# IEEEcounter.net
KiCad netlist of a schematic drawn in EAGLE
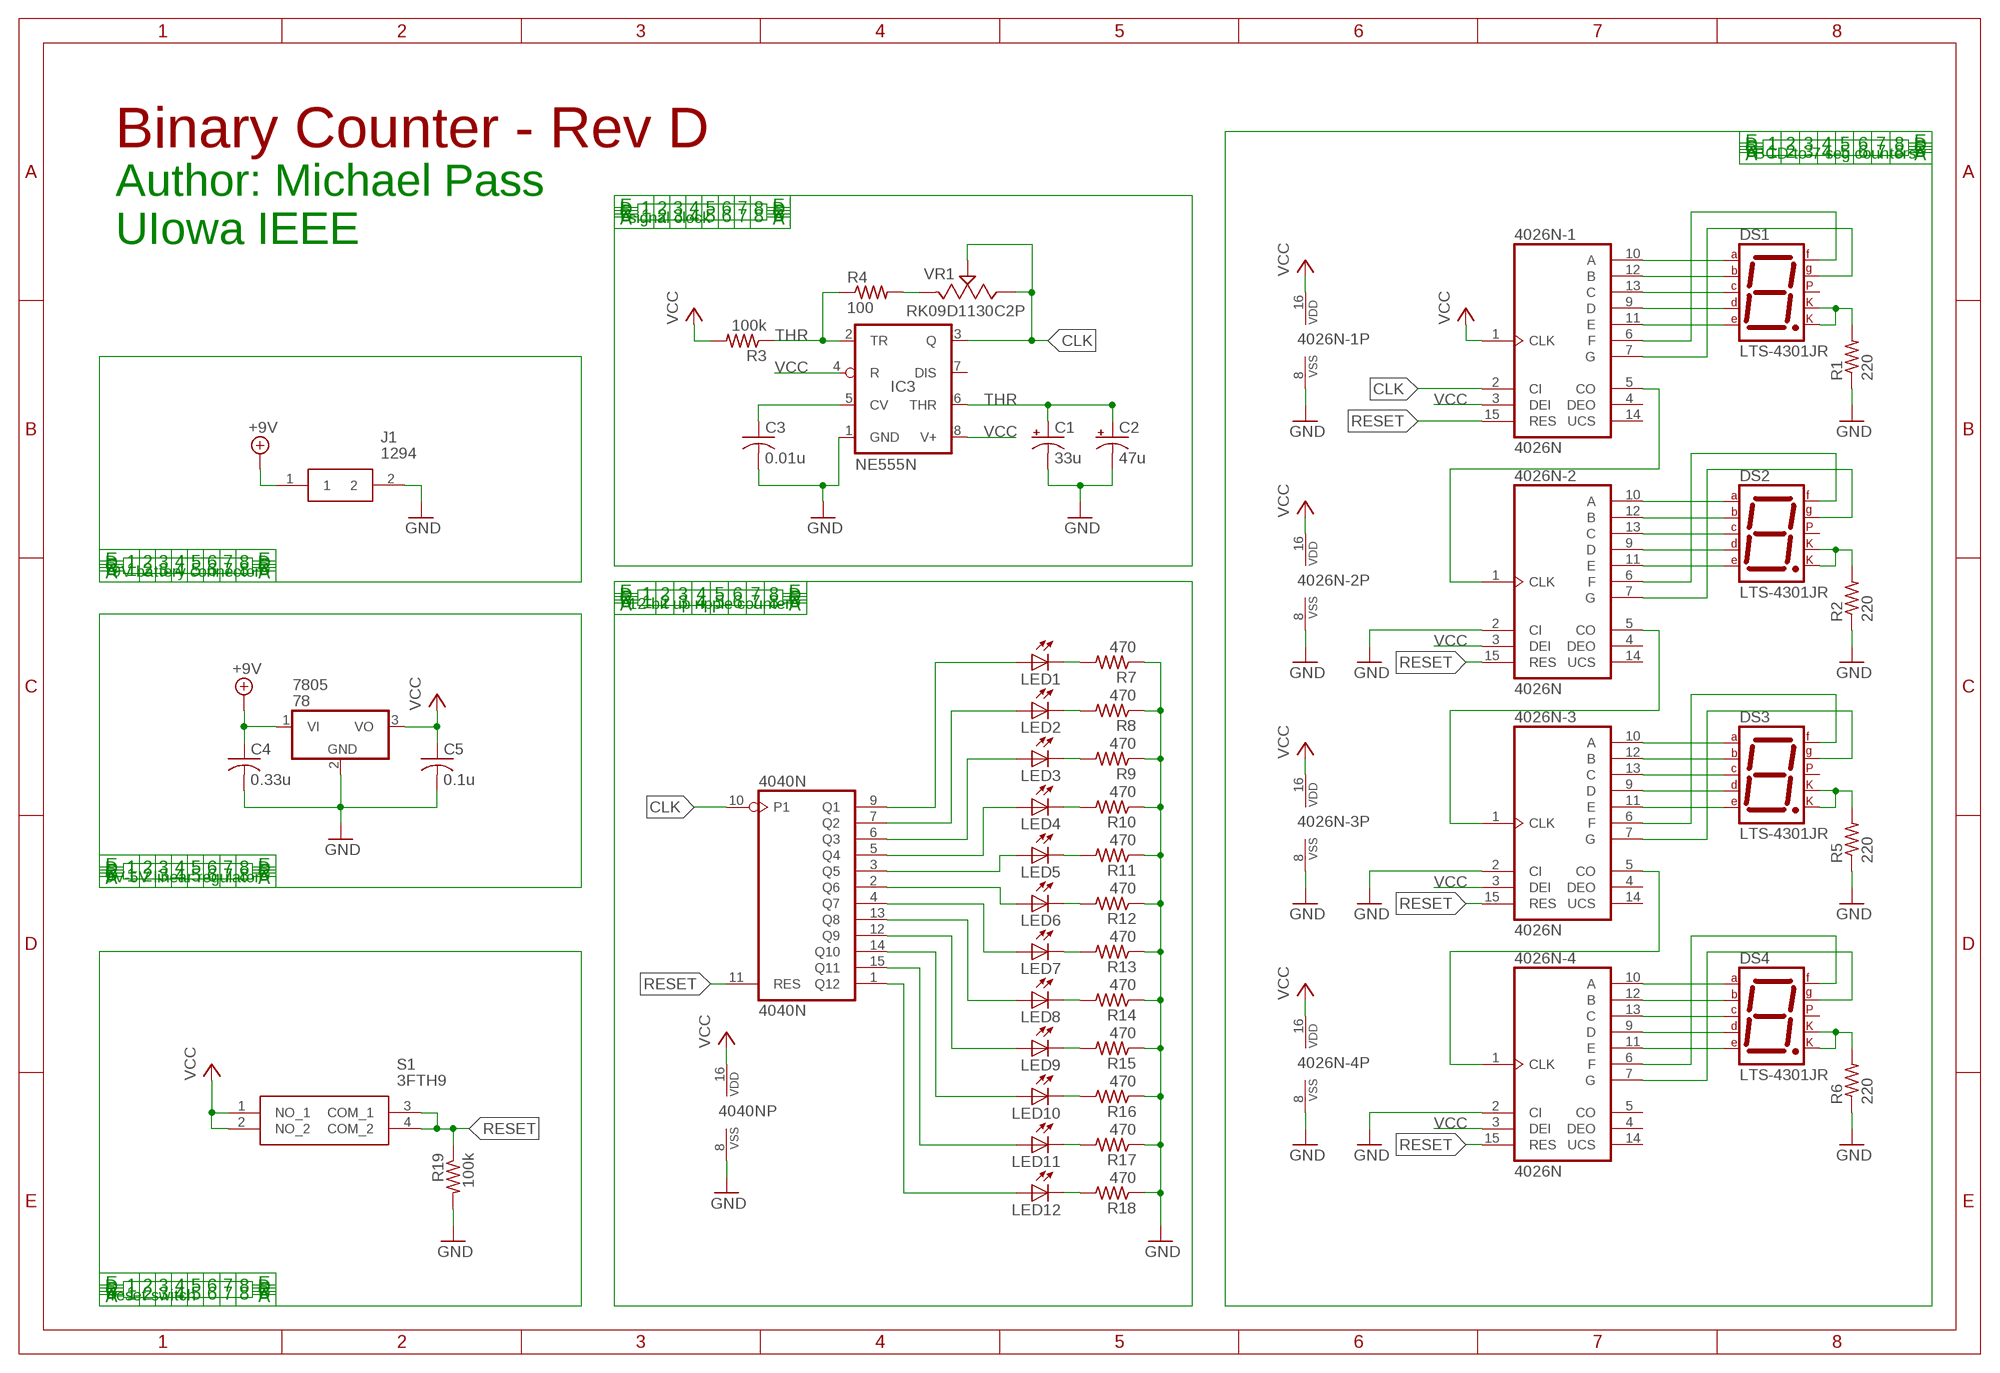
[diagram p0: schematic, sheet 1]

(export (version "E")
  (design (tool "Eeschema 10.0.6"))
  (components
    (comp (ref "4026N-1")
      (value "4026N")
      (footprint "eagle-import:DIL16")
      (libsource (lib "eagle-import") (part "4026N"))
    )
    (comp (ref "4026N-2")
      (value "4026N")
      (footprint "eagle-import:DIL16")
      (libsource (lib "eagle-import") (part "4026N"))
    )
    (comp (ref "4026N-3")
      (value "4026N")
      (footprint "eagle-import:DIL16")
      (libsource (lib "eagle-import") (part "4026N"))
    )
    (comp (ref "4026N-4")
      (value "4026N")
      (footprint "eagle-import:DIL16")
      (libsource (lib "eagle-import") (part "4026N"))
    )
    (comp (ref "4040N")
      (value "4040N")
      (footprint "eagle-import:DIL16")
      (libsource (lib "eagle-import") (part "4040N"))
    )
    (comp (ref "7805")
      (value "78")
      (footprint "eagle-import:TO220H")
      (libsource (lib "eagle-import") (part "78"))
    )
    (comp (ref "C1")
      (value "33u")
      (footprint "eagle-import:E2,5-6")
      (libsource (lib "eagle-import") (part "CPOL-USE2.5-6"))
    )
    (comp (ref "C2")
      (value "47u")
      (footprint "eagle-import:E2,5-6")
      (libsource (lib "eagle-import") (part "CPOL-USE2.5-6"))
    )
    (comp (ref "C3")
      (value "0.01u")
      (footprint "eagle-import:C050-025X075")
      (libsource (lib "eagle-import") (part "C-US050-025X075"))
    )
    (comp (ref "C4")
      (value "0.33u")
      (footprint "eagle-import:C1210")
      (libsource (lib "eagle-import") (part "C-USC1210"))
    )
    (comp (ref "C5")
      (value "0.1u")
      (footprint "eagle-import:C1210")
      (libsource (lib "eagle-import") (part "C-USC1210"))
    )
    (comp (ref "DS1")
      (value "LTS-4301JR")
      (footprint "eagle-import:DIPS762W50P254L1290H700Q10N")
      (fields (field (name "MOUSER_PART_NUMBER") "859-LTS-4301JR"))
      (libsource (lib "eagle-import") (part "LTS-4301JR"))
    )
    (comp (ref "DS2")
      (value "LTS-4301JR")
      (footprint "eagle-import:DIPS762W50P254L1290H700Q10N")
      (fields (field (name "MOUSER_PART_NUMBER") "859-LTS-4301JR"))
      (libsource (lib "eagle-import") (part "LTS-4301JR"))
    )
    (comp (ref "DS3")
      (value "LTS-4301JR")
      (footprint "eagle-import:DIPS762W50P254L1290H700Q10N")
      (fields (field (name "MOUSER_PART_NUMBER") "859-LTS-4301JR"))
      (libsource (lib "eagle-import") (part "LTS-4301JR"))
    )
    (comp (ref "DS4")
      (value "LTS-4301JR")
      (footprint "eagle-import:DIPS762W50P254L1290H700Q10N")
      (fields (field (name "MOUSER_PART_NUMBER") "859-LTS-4301JR"))
      (libsource (lib "eagle-import") (part "LTS-4301JR"))
    )
    (comp (ref "IC3")
      (value "NE555N")
      (footprint "eagle-import:DIL08")
      (libsource (lib "eagle-import") (part "555NNE"))
    )
    (comp (ref "J1")
      (value "1294")
      (footprint "eagle-import:1294")
      (fields (field (name "MOUSER_PART_NUMBER") "534-1294") (field (name "RS_PART_NUMBER") "1725845"))
      (libsource (lib "eagle-import") (part "1294"))
    )
    (comp (ref "LED1")
      (value "LED5MM")
      (footprint "eagle-import:LED5MM")
      (libsource (lib "eagle-import") (part "LED5MM"))
    )
    (comp (ref "LED2")
      (value "LED5MM")
      (footprint "eagle-import:LED5MM")
      (libsource (lib "eagle-import") (part "LED5MM"))
    )
    (comp (ref "LED3")
      (value "LED5MM")
      (footprint "eagle-import:LED5MM")
      (libsource (lib "eagle-import") (part "LED5MM"))
    )
    (comp (ref "LED4")
      (value "LED5MM")
      (footprint "eagle-import:LED5MM")
      (libsource (lib "eagle-import") (part "LED5MM"))
    )
    (comp (ref "LED5")
      (value "LED5MM")
      (footprint "eagle-import:LED5MM")
      (libsource (lib "eagle-import") (part "LED5MM"))
    )
    (comp (ref "LED6")
      (value "LED5MM")
      (footprint "eagle-import:LED5MM")
      (libsource (lib "eagle-import") (part "LED5MM"))
    )
    (comp (ref "LED7")
      (value "LED5MM")
      (footprint "eagle-import:LED5MM")
      (libsource (lib "eagle-import") (part "LED5MM"))
    )
    (comp (ref "LED8")
      (value "LED5MM")
      (footprint "eagle-import:LED5MM")
      (libsource (lib "eagle-import") (part "LED5MM"))
    )
    (comp (ref "LED9")
      (value "LED5MM")
      (footprint "eagle-import:LED5MM")
      (libsource (lib "eagle-import") (part "LED5MM"))
    )
    (comp (ref "LED10")
      (value "LED5MM")
      (footprint "eagle-import:LED5MM")
      (libsource (lib "eagle-import") (part "LED5MM"))
    )
    (comp (ref "LED11")
      (value "LED5MM")
      (footprint "eagle-import:LED5MM")
      (libsource (lib "eagle-import") (part "LED5MM"))
    )
    (comp (ref "LED12")
      (value "LED5MM")
      (footprint "eagle-import:LED5MM")
      (libsource (lib "eagle-import") (part "LED5MM"))
    )
    (comp (ref "R1")
      (value "220")
      (footprint "eagle-import:R1210")
      (libsource (lib "eagle-import") (part "R-US_R1210"))
    )
    (comp (ref "R2")
      (value "220")
      (footprint "eagle-import:R1210")
      (libsource (lib "eagle-import") (part "R-US_R1210"))
    )
    (comp (ref "R3")
      (value "100k")
      (footprint "eagle-import:R1210")
      (libsource (lib "eagle-import") (part "R-US_R1210"))
    )
    (comp (ref "R4")
      (value "100")
      (footprint "eagle-import:R1210")
      (libsource (lib "eagle-import") (part "R-US_R1210"))
    )
    (comp (ref "R5")
      (value "220")
      (footprint "eagle-import:R1210")
      (libsource (lib "eagle-import") (part "R-US_R1210"))
    )
    (comp (ref "R6")
      (value "220")
      (footprint "eagle-import:R1210")
      (libsource (lib "eagle-import") (part "R-US_R1210"))
    )
    (comp (ref "R7")
      (value "470")
      (footprint "eagle-import:R1210")
      (libsource (lib "eagle-import") (part "R-US_R1210"))
    )
    (comp (ref "R8")
      (value "470")
      (footprint "eagle-import:R1210")
      (libsource (lib "eagle-import") (part "R-US_R1210"))
    )
    (comp (ref "R9")
      (value "470")
      (footprint "eagle-import:R1210")
      (libsource (lib "eagle-import") (part "R-US_R1210"))
    )
    (comp (ref "R10")
      (value "470")
      (footprint "eagle-import:R1210")
      (libsource (lib "eagle-import") (part "R-US_R1210"))
    )
    (comp (ref "R11")
      (value "470")
      (footprint "eagle-import:R1210")
      (libsource (lib "eagle-import") (part "R-US_R1210"))
    )
    (comp (ref "R12")
      (value "470")
      (footprint "eagle-import:R1210")
      (libsource (lib "eagle-import") (part "R-US_R1210"))
    )
    (comp (ref "R13")
      (value "470")
      (footprint "eagle-import:R1210")
      (libsource (lib "eagle-import") (part "R-US_R1210"))
    )
    (comp (ref "R14")
      (value "470")
      (footprint "eagle-import:R1210")
      (libsource (lib "eagle-import") (part "R-US_R1210"))
    )
    (comp (ref "R15")
      (value "470")
      (footprint "eagle-import:R1210")
      (libsource (lib "eagle-import") (part "R-US_R1210"))
    )
    (comp (ref "R16")
      (value "470")
      (footprint "eagle-import:R1210")
      (libsource (lib "eagle-import") (part "R-US_R1210"))
    )
    (comp (ref "R17")
      (value "470")
      (footprint "eagle-import:R1210")
      (libsource (lib "eagle-import") (part "R-US_R1210"))
    )
    (comp (ref "R18")
      (value "470")
      (footprint "eagle-import:R1210")
      (libsource (lib "eagle-import") (part "R-US_R1210"))
    )
    (comp (ref "R19")
      (value "100k")
      (footprint "eagle-import:R1210")
      (libsource (lib "eagle-import") (part "R-US_R1210"))
    )
    (comp (ref "S1")
      (value "3FTH9")
      (footprint "eagle-import:3FTH9")
      (fields (field (name "MOUSER_PART_NUMBER") "642-3FTH9"))
      (libsource (lib "eagle-import") (part "3FTH9"))
    )
    (comp (ref "VR1")
      (value "RK09D1130C2P")
      (footprint "eagle-import:RK09D1130C3C")
      (fields
        (field (name "MOUSER_PART_NUMBER") "688-RK09D1130C2P")
        (field (name "RS_PART_NUMBER") "1726272")
      )
      (libsource (lib "eagle-import") (part "RK09D1130C2P"))
    )
  )
  (nets
    (net (code "1") (name "+9V") (class "Default")
      (node (ref "7805") (pin "1") (pinfunction "VI_1") (pintype "input"))
      (node (ref "C4") (pin "1") (pinfunction "1_1") (pintype "passive"))
      (node (ref "J1") (pin "1") (pinfunction "1_1") (pintype "bidirectional"))
    )
    (net (code "2") (name "/THR") (class "Default")
      (node (ref "C1") (pin "+") (pinfunction "+_+") (pintype "passive"))
      (node (ref "C2") (pin "+") (pinfunction "+_+") (pintype "passive"))
      (node (ref "IC3") (pin "2") (pinfunction "TR_2") (pintype "input"))
      (node (ref "IC3") (pin "6") (pinfunction "THR_6") (pintype "input"))
      (node (ref "R3") (pin "1") (pinfunction "1_1") (pintype "passive"))
      (node (ref "R4") (pin "1") (pinfunction "1_1") (pintype "passive"))
    )
    (net (code "3") (name "CLK") (class "Default")
      (node (ref "4026N-1") (pin "2") (pinfunction "CI_2") (pintype "input"))
      (node (ref "4040N") (pin "10") (pinfunction "P1_10") (pintype "input"))
      (node (ref "IC3") (pin "3") (pinfunction "Q_3") (pintype "output"))
      (node (ref "VR1") (pin "2") (pinfunction "2_2") (pintype "passive"))
      (node (ref "VR1") (pin "3") (pinfunction "3_3") (pintype "passive"))
    )
    (net (code "4") (name "GND") (class "Default")
      (node (ref "4026N-1") (pin "8") (pinfunction "VSS_8") (pintype "power_in"))
      (node (ref "4026N-2") (pin "2") (pinfunction "CI_2") (pintype "input"))
      (node (ref "4026N-2") (pin "8") (pinfunction "VSS_8") (pintype "power_in"))
      (node (ref "4026N-3") (pin "2") (pinfunction "CI_2") (pintype "input"))
      (node (ref "4026N-3") (pin "8") (pinfunction "VSS_8") (pintype "power_in"))
      (node (ref "4026N-4") (pin "2") (pinfunction "CI_2") (pintype "input"))
      (node (ref "4026N-4") (pin "8") (pinfunction "VSS_8") (pintype "power_in"))
      (node (ref "4040N") (pin "8") (pinfunction "VSS_8") (pintype "power_in"))
      (node (ref "7805") (pin "2") (pinfunction "GND_2") (pintype "passive"))
      (node (ref "C1") (pin "-") (pinfunction "-_-") (pintype "passive"))
      (node (ref "C2") (pin "-") (pinfunction "-_-") (pintype "passive"))
      (node (ref "C3") (pin "2") (pinfunction "2_2") (pintype "passive"))
      (node (ref "C4") (pin "2") (pinfunction "2_2") (pintype "passive"))
      (node (ref "C5") (pin "2") (pinfunction "2_2") (pintype "passive"))
      (node (ref "IC3") (pin "1") (pinfunction "GND_1") (pintype "power_in"))
      (node (ref "J1") (pin "2") (pinfunction "2_2") (pintype "bidirectional"))
      (node (ref "R1") (pin "1") (pinfunction "1_1") (pintype "passive"))
      (node (ref "R10") (pin "1") (pinfunction "1_1") (pintype "passive"))
      (node (ref "R11") (pin "1") (pinfunction "1_1") (pintype "passive"))
      (node (ref "R12") (pin "1") (pinfunction "1_1") (pintype "passive"))
      (node (ref "R13") (pin "1") (pinfunction "1_1") (pintype "passive"))
      (node (ref "R14") (pin "1") (pinfunction "1_1") (pintype "passive"))
      (node (ref "R15") (pin "1") (pinfunction "1_1") (pintype "passive"))
      (node (ref "R16") (pin "1") (pinfunction "1_1") (pintype "passive"))
      (node (ref "R17") (pin "1") (pinfunction "1_1") (pintype "passive"))
      (node (ref "R18") (pin "1") (pinfunction "1_1") (pintype "passive"))
      (node (ref "R19") (pin "2") (pinfunction "2_2") (pintype "passive"))
      (node (ref "R2") (pin "1") (pinfunction "1_1") (pintype "passive"))
      (node (ref "R5") (pin "1") (pinfunction "1_1") (pintype "passive"))
      (node (ref "R6") (pin "1") (pinfunction "1_1") (pintype "passive"))
      (node (ref "R7") (pin "1") (pinfunction "1_1") (pintype "passive"))
      (node (ref "R8") (pin "1") (pinfunction "1_1") (pintype "passive"))
      (node (ref "R9") (pin "1") (pinfunction "1_1") (pintype "passive"))
    )
    (net (code "5") (name "Net-(4026N-1A-A)") (class "Default")
      (node (ref "4026N-1") (pin "10") (pinfunction "A_10") (pintype "output"))
      (node (ref "DS1") (pin "10") (pinfunction "A_10") (pintype "passive"))
    )
    (net (code "6") (name "Net-(4026N-1A-B)") (class "Default")
      (node (ref "4026N-1") (pin "12") (pinfunction "B_12") (pintype "output"))
      (node (ref "DS1") (pin "9") (pinfunction "B_9") (pintype "passive"))
    )
    (net (code "7") (name "Net-(4026N-1A-C)") (class "Default")
      (node (ref "4026N-1") (pin "13") (pinfunction "C_13") (pintype "output"))
      (node (ref "DS1") (pin "7") (pinfunction "C_7") (pintype "passive"))
    )
    (net (code "8") (name "Net-(4026N-1A-CO)") (class "Default")
      (node (ref "4026N-1") (pin "5") (pinfunction "CO_5") (pintype "output"))
      (node (ref "4026N-2") (pin "1") (pinfunction "CLK_1") (pintype "input"))
    )
    (net (code "9") (name "Net-(4026N-1A-D)") (class "Default")
      (node (ref "4026N-1") (pin "9") (pinfunction "D_9") (pintype "output"))
      (node (ref "DS1") (pin "5") (pinfunction "D_5") (pintype "passive"))
    )
    (net (code "10") (name "Net-(4026N-1A-E)") (class "Default")
      (node (ref "4026N-1") (pin "11") (pinfunction "E_11") (pintype "output"))
      (node (ref "DS1") (pin "4") (pinfunction "E_4") (pintype "passive"))
    )
    (net (code "11") (name "Net-(4026N-1A-F)") (class "Default")
      (node (ref "4026N-1") (pin "6") (pinfunction "F_6") (pintype "output"))
      (node (ref "DS1") (pin "2") (pinfunction "F_2") (pintype "passive"))
    )
    (net (code "12") (name "Net-(4026N-1A-G)") (class "Default")
      (node (ref "4026N-1") (pin "7") (pinfunction "G_7") (pintype "output"))
      (node (ref "DS1") (pin "1") (pinfunction "G_1") (pintype "passive"))
    )
    (net (code "13") (name "Net-(4026N-2A-A)") (class "Default")
      (node (ref "4026N-2") (pin "10") (pinfunction "A_10") (pintype "output"))
      (node (ref "DS2") (pin "10") (pinfunction "A_10") (pintype "passive"))
    )
    (net (code "14") (name "Net-(4026N-2A-B)") (class "Default")
      (node (ref "4026N-2") (pin "12") (pinfunction "B_12") (pintype "output"))
      (node (ref "DS2") (pin "9") (pinfunction "B_9") (pintype "passive"))
    )
    (net (code "15") (name "Net-(4026N-2A-C)") (class "Default")
      (node (ref "4026N-2") (pin "13") (pinfunction "C_13") (pintype "output"))
      (node (ref "DS2") (pin "7") (pinfunction "C_7") (pintype "passive"))
    )
    (net (code "16") (name "Net-(4026N-2A-CO)") (class "Default")
      (node (ref "4026N-2") (pin "5") (pinfunction "CO_5") (pintype "output"))
      (node (ref "4026N-3") (pin "1") (pinfunction "CLK_1") (pintype "input"))
    )
    (net (code "17") (name "Net-(4026N-2A-D)") (class "Default")
      (node (ref "4026N-2") (pin "9") (pinfunction "D_9") (pintype "output"))
      (node (ref "DS2") (pin "5") (pinfunction "D_5") (pintype "passive"))
    )
    (net (code "18") (name "Net-(4026N-2A-E)") (class "Default")
      (node (ref "4026N-2") (pin "11") (pinfunction "E_11") (pintype "output"))
      (node (ref "DS2") (pin "4") (pinfunction "E_4") (pintype "passive"))
    )
    (net (code "19") (name "Net-(4026N-2A-F)") (class "Default")
      (node (ref "4026N-2") (pin "6") (pinfunction "F_6") (pintype "output"))
      (node (ref "DS2") (pin "2") (pinfunction "F_2") (pintype "passive"))
    )
    (net (code "20") (name "Net-(4026N-2A-G)") (class "Default")
      (node (ref "4026N-2") (pin "7") (pinfunction "G_7") (pintype "output"))
      (node (ref "DS2") (pin "1") (pinfunction "G_1") (pintype "passive"))
    )
    (net (code "21") (name "Net-(4026N-3A-A)") (class "Default")
      (node (ref "4026N-3") (pin "10") (pinfunction "A_10") (pintype "output"))
      (node (ref "DS3") (pin "10") (pinfunction "A_10") (pintype "passive"))
    )
    (net (code "22") (name "Net-(4026N-3A-B)") (class "Default")
      (node (ref "4026N-3") (pin "12") (pinfunction "B_12") (pintype "output"))
      (node (ref "DS3") (pin "9") (pinfunction "B_9") (pintype "passive"))
    )
    (net (code "23") (name "Net-(4026N-3A-C)") (class "Default")
      (node (ref "4026N-3") (pin "13") (pinfunction "C_13") (pintype "output"))
      (node (ref "DS3") (pin "7") (pinfunction "C_7") (pintype "passive"))
    )
    (net (code "24") (name "Net-(4026N-3A-CO)") (class "Default")
      (node (ref "4026N-3") (pin "5") (pinfunction "CO_5") (pintype "output"))
      (node (ref "4026N-4") (pin "1") (pinfunction "CLK_1") (pintype "input"))
    )
    (net (code "25") (name "Net-(4026N-3A-D)") (class "Default")
      (node (ref "4026N-3") (pin "9") (pinfunction "D_9") (pintype "output"))
      (node (ref "DS3") (pin "5") (pinfunction "D_5") (pintype "passive"))
    )
    (net (code "26") (name "Net-(4026N-3A-E)") (class "Default")
      (node (ref "4026N-3") (pin "11") (pinfunction "E_11") (pintype "output"))
      (node (ref "DS3") (pin "4") (pinfunction "E_4") (pintype "passive"))
    )
    (net (code "27") (name "Net-(4026N-3A-F)") (class "Default")
      (node (ref "4026N-3") (pin "6") (pinfunction "F_6") (pintype "output"))
      (node (ref "DS3") (pin "2") (pinfunction "F_2") (pintype "passive"))
    )
    (net (code "28") (name "Net-(4026N-3A-G)") (class "Default")
      (node (ref "4026N-3") (pin "7") (pinfunction "G_7") (pintype "output"))
      (node (ref "DS3") (pin "1") (pinfunction "G_1") (pintype "passive"))
    )
    (net (code "29") (name "Net-(4026N-4A-A)") (class "Default")
      (node (ref "4026N-4") (pin "10") (pinfunction "A_10") (pintype "output"))
      (node (ref "DS4") (pin "10") (pinfunction "A_10") (pintype "passive"))
    )
    (net (code "30") (name "Net-(4026N-4A-B)") (class "Default")
      (node (ref "4026N-4") (pin "12") (pinfunction "B_12") (pintype "output"))
      (node (ref "DS4") (pin "9") (pinfunction "B_9") (pintype "passive"))
    )
    (net (code "31") (name "Net-(4026N-4A-C)") (class "Default")
      (node (ref "4026N-4") (pin "13") (pinfunction "C_13") (pintype "output"))
      (node (ref "DS4") (pin "7") (pinfunction "C_7") (pintype "passive"))
    )
    (net (code "32") (name "Net-(4026N-4A-D)") (class "Default")
      (node (ref "4026N-4") (pin "9") (pinfunction "D_9") (pintype "output"))
      (node (ref "DS4") (pin "5") (pinfunction "D_5") (pintype "passive"))
    )
    (net (code "33") (name "Net-(4026N-4A-E)") (class "Default")
      (node (ref "4026N-4") (pin "11") (pinfunction "E_11") (pintype "output"))
      (node (ref "DS4") (pin "4") (pinfunction "E_4") (pintype "passive"))
    )
    (net (code "34") (name "Net-(4026N-4A-F)") (class "Default")
      (node (ref "4026N-4") (pin "6") (pinfunction "F_6") (pintype "output"))
      (node (ref "DS4") (pin "2") (pinfunction "F_2") (pintype "passive"))
    )
    (net (code "35") (name "Net-(4026N-4A-G)") (class "Default")
      (node (ref "4026N-4") (pin "7") (pinfunction "G_7") (pintype "output"))
      (node (ref "DS4") (pin "1") (pinfunction "G_1") (pintype "passive"))
    )
    (net (code "36") (name "Net-(4040NA-Q1)") (class "Default")
      (node (ref "4040N") (pin "9") (pinfunction "Q1_9") (pintype "output"))
      (node (ref "LED1") (pin "A") (pinfunction "A_A") (pintype "passive"))
    )
    (net (code "37") (name "Net-(4040NA-Q2)") (class "Default")
      (node (ref "4040N") (pin "7") (pinfunction "Q2_7") (pintype "output"))
      (node (ref "LED2") (pin "A") (pinfunction "A_A") (pintype "passive"))
    )
    (net (code "38") (name "Net-(4040NA-Q3)") (class "Default")
      (node (ref "4040N") (pin "6") (pinfunction "Q3_6") (pintype "output"))
      (node (ref "LED3") (pin "A") (pinfunction "A_A") (pintype "passive"))
    )
    (net (code "39") (name "Net-(4040NA-Q4)") (class "Default")
      (node (ref "4040N") (pin "5") (pinfunction "Q4_5") (pintype "output"))
      (node (ref "LED4") (pin "A") (pinfunction "A_A") (pintype "passive"))
    )
    (net (code "40") (name "Net-(4040NA-Q5)") (class "Default")
      (node (ref "4040N") (pin "3") (pinfunction "Q5_3") (pintype "output"))
      (node (ref "LED5") (pin "A") (pinfunction "A_A") (pintype "passive"))
    )
    (net (code "41") (name "Net-(4040NA-Q6)") (class "Default")
      (node (ref "4040N") (pin "2") (pinfunction "Q6_2") (pintype "output"))
      (node (ref "LED6") (pin "A") (pinfunction "A_A") (pintype "passive"))
    )
    (net (code "42") (name "Net-(4040NA-Q7)") (class "Default")
      (node (ref "4040N") (pin "4") (pinfunction "Q7_4") (pintype "output"))
      (node (ref "LED7") (pin "A") (pinfunction "A_A") (pintype "passive"))
    )
    (net (code "43") (name "Net-(4040NA-Q8)") (class "Default")
      (node (ref "4040N") (pin "13") (pinfunction "Q8_13") (pintype "output"))
      (node (ref "LED8") (pin "A") (pinfunction "A_A") (pintype "passive"))
    )
    (net (code "44") (name "Net-(4040NA-Q9)") (class "Default")
      (node (ref "4040N") (pin "12") (pinfunction "Q9_12") (pintype "output"))
      (node (ref "LED9") (pin "A") (pinfunction "A_A") (pintype "passive"))
    )
    (net (code "45") (name "Net-(4040NA-Q10)") (class "Default")
      (node (ref "4040N") (pin "14") (pinfunction "Q10_14") (pintype "output"))
      (node (ref "LED10") (pin "A") (pinfunction "A_A") (pintype "passive"))
    )
    (net (code "46") (name "Net-(4040NA-Q11)") (class "Default")
      (node (ref "4040N") (pin "15") (pinfunction "Q11_15") (pintype "output"))
      (node (ref "LED11") (pin "A") (pinfunction "A_A") (pintype "passive"))
    )
    (net (code "47") (name "Net-(4040NA-Q12)") (class "Default")
      (node (ref "4040N") (pin "1") (pinfunction "Q12_1") (pintype "output"))
      (node (ref "LED12") (pin "A") (pinfunction "A_A") (pintype "passive"))
    )
    (net (code "48") (name "Net-(DS1-CK1)") (class "Default")
      (node (ref "DS1") (pin "3") (pinfunction "CK1_3") (pintype "passive"))
      (node (ref "DS1") (pin "8") (pinfunction "CK2_8") (pintype "passive"))
      (node (ref "R1") (pin "2") (pinfunction "2_2") (pintype "passive"))
    )
    (net (code "49") (name "Net-(DS2-CK1)") (class "Default")
      (node (ref "DS2") (pin "3") (pinfunction "CK1_3") (pintype "passive"))
      (node (ref "DS2") (pin "8") (pinfunction "CK2_8") (pintype "passive"))
      (node (ref "R2") (pin "2") (pinfunction "2_2") (pintype "passive"))
    )
    (net (code "50") (name "Net-(DS3-CK1)") (class "Default")
      (node (ref "DS3") (pin "3") (pinfunction "CK1_3") (pintype "passive"))
      (node (ref "DS3") (pin "8") (pinfunction "CK2_8") (pintype "passive"))
      (node (ref "R5") (pin "2") (pinfunction "2_2") (pintype "passive"))
    )
    (net (code "51") (name "Net-(DS4-CK1)") (class "Default")
      (node (ref "DS4") (pin "3") (pinfunction "CK1_3") (pintype "passive"))
      (node (ref "DS4") (pin "8") (pinfunction "CK2_8") (pintype "passive"))
      (node (ref "R6") (pin "2") (pinfunction "2_2") (pintype "passive"))
    )
    (net (code "52") (name "Net-(IC3-CV)") (class "Default")
      (node (ref "C3") (pin "1") (pinfunction "1_1") (pintype "passive"))
      (node (ref "IC3") (pin "5") (pinfunction "CV_5") (pintype "input"))
    )
    (net (code "53") (name "Net-(LED1-C)") (class "Default")
      (node (ref "LED1") (pin "K") (pinfunction "C_K") (pintype "passive"))
      (node (ref "R7") (pin "2") (pinfunction "2_2") (pintype "passive"))
    )
    (net (code "54") (name "Net-(LED2-C)") (class "Default")
      (node (ref "LED2") (pin "K") (pinfunction "C_K") (pintype "passive"))
      (node (ref "R8") (pin "2") (pinfunction "2_2") (pintype "passive"))
    )
    (net (code "55") (name "Net-(LED3-C)") (class "Default")
      (node (ref "LED3") (pin "K") (pinfunction "C_K") (pintype "passive"))
      (node (ref "R9") (pin "2") (pinfunction "2_2") (pintype "passive"))
    )
    (net (code "56") (name "Net-(LED4-C)") (class "Default")
      (node (ref "LED4") (pin "K") (pinfunction "C_K") (pintype "passive"))
      (node (ref "R10") (pin "2") (pinfunction "2_2") (pintype "passive"))
    )
    (net (code "57") (name "Net-(LED5-C)") (class "Default")
      (node (ref "LED5") (pin "K") (pinfunction "C_K") (pintype "passive"))
      (node (ref "R11") (pin "2") (pinfunction "2_2") (pintype "passive"))
    )
    (net (code "58") (name "Net-(LED6-C)") (class "Default")
      (node (ref "LED6") (pin "K") (pinfunction "C_K") (pintype "passive"))
      (node (ref "R12") (pin "2") (pinfunction "2_2") (pintype "passive"))
    )
    (net (code "59") (name "Net-(LED7-C)") (class "Default")
      (node (ref "LED7") (pin "K") (pinfunction "C_K") (pintype "passive"))
      (node (ref "R13") (pin "2") (pinfunction "2_2") (pintype "passive"))
    )
    (net (code "60") (name "Net-(LED8-C)") (class "Default")
      (node (ref "LED8") (pin "K") (pinfunction "C_K") (pintype "passive"))
      (node (ref "R14") (pin "2") (pinfunction "2_2") (pintype "passive"))
    )
    (net (code "61") (name "Net-(LED9-C)") (class "Default")
      (node (ref "LED9") (pin "K") (pinfunction "C_K") (pintype "passive"))
      (node (ref "R15") (pin "2") (pinfunction "2_2") (pintype "passive"))
    )
    (net (code "62") (name "Net-(LED10-C)") (class "Default")
      (node (ref "LED10") (pin "K") (pinfunction "C_K") (pintype "passive"))
      (node (ref "R16") (pin "2") (pinfunction "2_2") (pintype "passive"))
    )
    (net (code "63") (name "Net-(LED11-C)") (class "Default")
      (node (ref "LED11") (pin "K") (pinfunction "C_K") (pintype "passive"))
      (node (ref "R17") (pin "2") (pinfunction "2_2") (pintype "passive"))
    )
    (net (code "64") (name "Net-(LED12-C)") (class "Default")
      (node (ref "LED12") (pin "K") (pinfunction "C_K") (pintype "passive"))
      (node (ref "R18") (pin "2") (pinfunction "2_2") (pintype "passive"))
    )
    (net (code "65") (name "Net-(R4-Pad2)") (class "Default")
      (node (ref "R4") (pin "2") (pinfunction "2_2") (pintype "passive"))
      (node (ref "VR1") (pin "1") (pinfunction "1_1") (pintype "passive"))
    )
    (net (code "66") (name "RESET") (class "Default")
      (node (ref "4026N-1") (pin "15") (pinfunction "RES_15") (pintype "input"))
      (node (ref "4026N-2") (pin "15") (pinfunction "RES_15") (pintype "input"))
      (node (ref "4026N-3") (pin "15") (pinfunction "RES_15") (pintype "input"))
      (node (ref "4026N-4") (pin "15") (pinfunction "RES_15") (pintype "input"))
      (node (ref "4040N") (pin "11") (pinfunction "RES_11") (pintype "input"))
      (node (ref "R19") (pin "1") (pinfunction "1_1") (pintype "passive"))
      (node (ref "S1") (pin "3") (pinfunction "COM_1_3") (pintype "bidirectional"))
      (node (ref "S1") (pin "4") (pinfunction "COM_2_4") (pintype "bidirectional"))
    )
    (net (code "67") (name "VCC") (class "Default")
      (node (ref "4026N-1") (pin "1") (pinfunction "CLK_1") (pintype "input"))
      (node (ref "4026N-1") (pin "16") (pinfunction "VDD_16") (pintype "power_in"))
      (node (ref "4026N-1") (pin "3") (pinfunction "DEI_3") (pintype "input"))
      (node (ref "4026N-2") (pin "16") (pinfunction "VDD_16") (pintype "power_in"))
      (node (ref "4026N-2") (pin "3") (pinfunction "DEI_3") (pintype "input"))
      (node (ref "4026N-3") (pin "16") (pinfunction "VDD_16") (pintype "power_in"))
      (node (ref "4026N-3") (pin "3") (pinfunction "DEI_3") (pintype "input"))
      (node (ref "4026N-4") (pin "16") (pinfunction "VDD_16") (pintype "power_in"))
      (node (ref "4026N-4") (pin "3") (pinfunction "DEI_3") (pintype "input"))
      (node (ref "4040N") (pin "16") (pinfunction "VDD_16") (pintype "power_in"))
      (node (ref "7805") (pin "3") (pinfunction "VO_3") (pintype "passive"))
      (node (ref "C5") (pin "1") (pinfunction "1_1") (pintype "passive"))
      (node (ref "IC3") (pin "4") (pinfunction "R_4") (pintype "input"))
      (node (ref "IC3") (pin "8") (pinfunction "V+_8") (pintype "power_in"))
      (node (ref "R3") (pin "2") (pinfunction "2_2") (pintype "passive"))
      (node (ref "S1") (pin "1") (pinfunction "NO_1_1") (pintype "bidirectional"))
      (node (ref "S1") (pin "2") (pinfunction "NO_2_2") (pintype "bidirectional"))
    )
    (net (code "68") (name "unconnected-(4026N-1A-DEO-Pad4)") (class "Default")
      (node (ref "4026N-1") (pin "4") (pinfunction "DEO_4") (pintype "output"))
    )
    (net (code "69") (name "unconnected-(4026N-1A-UCS-Pad14)") (class "Default")
      (node (ref "4026N-1") (pin "14") (pinfunction "UCS_14") (pintype "output"))
    )
    (net (code "70") (name "unconnected-(4026N-2A-DEO-Pad4)") (class "Default")
      (node (ref "4026N-2") (pin "4") (pinfunction "DEO_4") (pintype "output"))
    )
    (net (code "71") (name "unconnected-(4026N-2A-UCS-Pad14)") (class "Default")
      (node (ref "4026N-2") (pin "14") (pinfunction "UCS_14") (pintype "output"))
    )
    (net (code "72") (name "unconnected-(4026N-3A-DEO-Pad4)") (class "Default")
      (node (ref "4026N-3") (pin "4") (pinfunction "DEO_4") (pintype "output"))
    )
    (net (code "73") (name "unconnected-(4026N-3A-UCS-Pad14)") (class "Default")
      (node (ref "4026N-3") (pin "14") (pinfunction "UCS_14") (pintype "output"))
    )
    (net (code "74") (name "unconnected-(4026N-4A-CO-Pad5)") (class "Default")
      (node (ref "4026N-4") (pin "5") (pinfunction "CO_5") (pintype "output"))
    )
    (net (code "75") (name "unconnected-(4026N-4A-DEO-Pad4)") (class "Default")
      (node (ref "4026N-4") (pin "4") (pinfunction "DEO_4") (pintype "output"))
    )
    (net (code "76") (name "unconnected-(4026N-4A-UCS-Pad14)") (class "Default")
      (node (ref "4026N-4") (pin "14") (pinfunction "UCS_14") (pintype "output"))
    )
    (net (code "77") (name "unconnected-(DS1-DP-Pad6)") (class "Default")
      (node (ref "DS1") (pin "6") (pinfunction "DP_6") (pintype "passive"))
    )
    (net (code "78") (name "unconnected-(DS2-DP-Pad6)") (class "Default")
      (node (ref "DS2") (pin "6") (pinfunction "DP_6") (pintype "passive"))
    )
    (net (code "79") (name "unconnected-(DS3-DP-Pad6)") (class "Default")
      (node (ref "DS3") (pin "6") (pinfunction "DP_6") (pintype "passive"))
    )
    (net (code "80") (name "unconnected-(DS4-DP-Pad6)") (class "Default")
      (node (ref "DS4") (pin "6") (pinfunction "DP_6") (pintype "passive"))
    )
    (net (code "81") (name "unconnected-(IC3-DIS-Pad7)") (class "Default")
      (node (ref "IC3") (pin "7") (pinfunction "DIS_7") (pintype "input"))
    )
  )
)
